# BLOCK1.net
KiCad netlist of a schematic drawn in Altium Designer
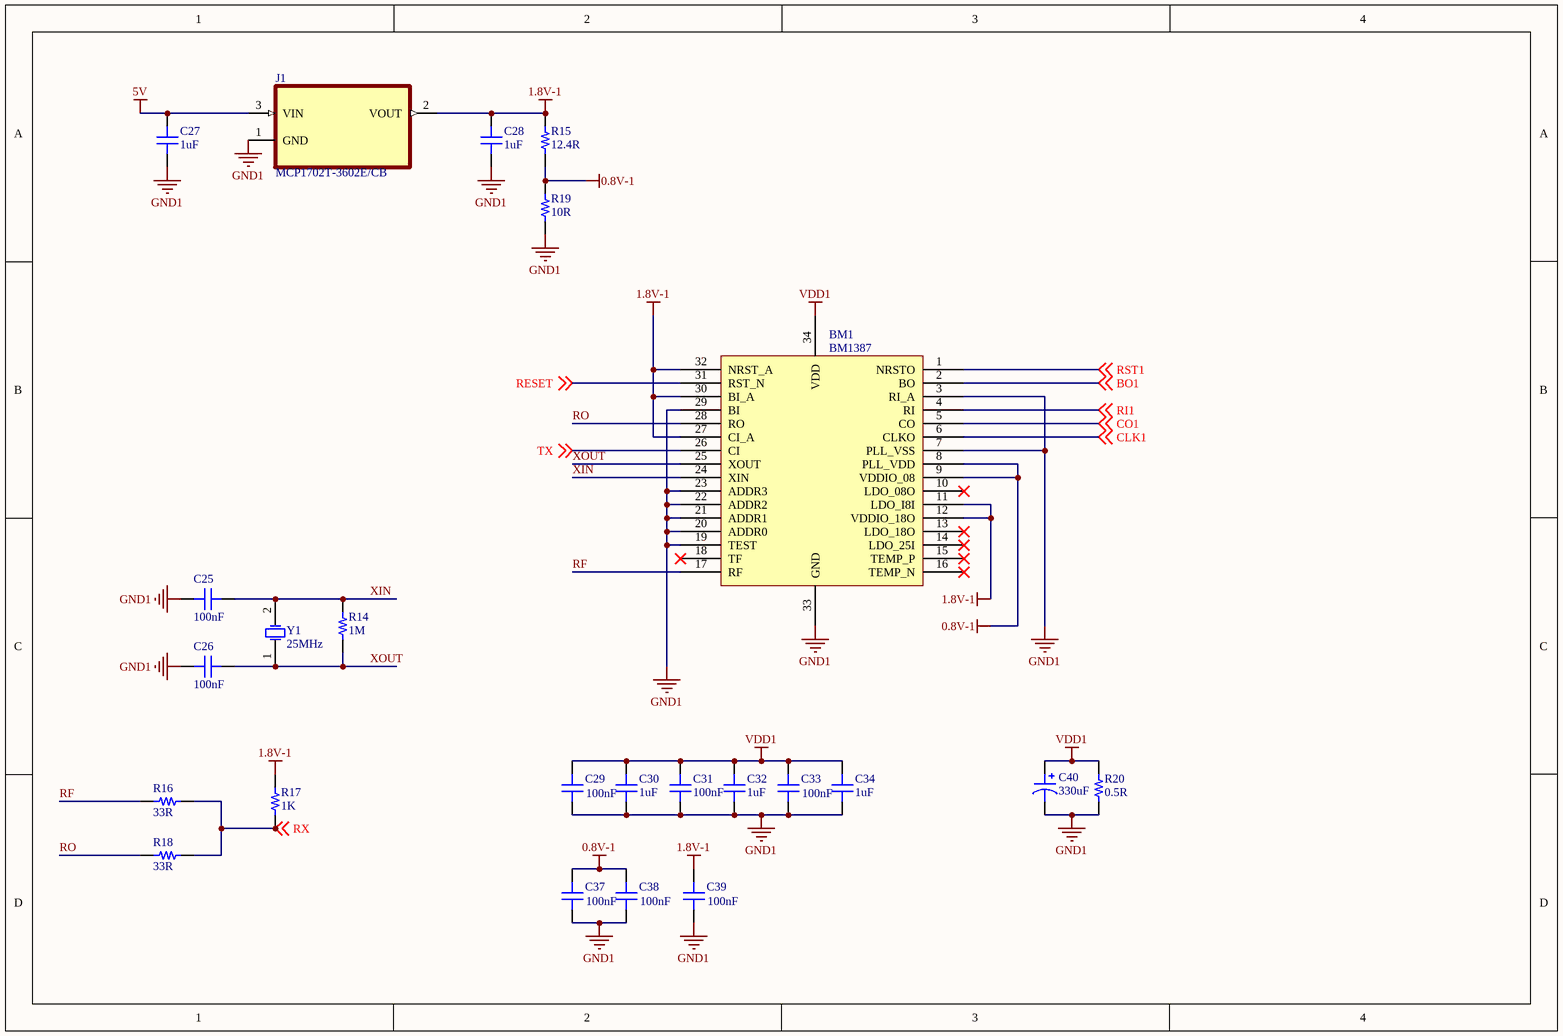
[diagram p0: BLOCK1.SchDoc]

(export (version "E")
  (design (tool "Eeschema 10.0.6"))
  (components
    (comp (ref "BM1") (value "BM1387") (footprint "BM1387") (libsource (lib "USB_MINER") (part "BM1387")))
    (comp (ref "C25") (value "100nF") (footprint "CAP-SMD-0402") (libsource (lib "USB_MINER") (part "CAP")))
    (comp (ref "C26") (value "100nF") (footprint "CAP-SMD-0402") (libsource (lib "USB_MINER") (part "CAP")))
    (comp (ref "C27") (value "1uF") (footprint "CAP-SMD-0402") (libsource (lib "USB_MINER") (part "CAP")))
    (comp (ref "C28") (value "1uF") (footprint "CAP-SMD-0402") (libsource (lib "USB_MINER") (part "CAP")))
    (comp (ref "C29") (value "100nF") (footprint "CAP_SMD_1206") (libsource (lib "USB_MINER") (part "CAP")))
    (comp (ref "C30") (value "1uF") (footprint "CAP_SMD_1206") (libsource (lib "USB_MINER") (part "CAP")))
    (comp (ref "C31") (value "100nF") (footprint "CAP_SMD_1206") (libsource (lib "USB_MINER") (part "CAP")))
    (comp (ref "C32") (value "1uF") (footprint "CAP_SMD_1206") (libsource (lib "USB_MINER") (part "CAP")))
    (comp (ref "C33") (value "100nF") (footprint "CAP_SMD_1206") (libsource (lib "USB_MINER") (part "CAP")))
    (comp (ref "C34") (value "1uF") (footprint "CAP_SMD_1206") (libsource (lib "USB_MINER") (part "CAP")))
    (comp (ref "C37") (value "100nF") (footprint "CAP-SMD-0402") (libsource (lib "USB_MINER") (part "CAP")))
    (comp (ref "C38") (value "100nF") (footprint "CAP-SMD-0402") (libsource (lib "USB_MINER") (part "CAP")))
    (comp (ref "C39") (value "100nF") (footprint "CAP-SMD-0402") (libsource (lib "USB_MINER") (part "CAP")))
    (comp (ref "C40")
      (value "330uF")
      (footprint "CAP-TAN-CASE-E")
      (libsource (lib "USB_MINER") (part "POLARIZED CAP"))
    )
    (comp (ref "J1")
      (value "MCP1702T-3602E/CB")
      (footprint "SOT95P255X145-3N")
      (description "250 mA Low Quiescent Current LDO Regulator")
      (libsource (lib "USB_MINER") (part "MCP1702T-3602E/CB"))
    )
    (comp (ref "R14") (value "1M") (footprint "RES-SMD-0402") (libsource (lib "USB_MINER") (part "RES")))
    (comp (ref "R15") (value "12.4R") (footprint "RES-SMD-0402") (libsource (lib "USB_MINER") (part "RES")))
    (comp (ref "R16") (value "33R") (footprint "RES-SMD-0402") (libsource (lib "USB_MINER") (part "RES")))
    (comp (ref "R17") (value "1K") (footprint "RES-SMD-0402") (libsource (lib "USB_MINER") (part "RES")))
    (comp (ref "R18") (value "33R") (footprint "RES-SMD-0402") (libsource (lib "USB_MINER") (part "RES")))
    (comp (ref "R19") (value "10R") (footprint "RES-SMD-0402") (libsource (lib "USB_MINER") (part "RES")))
    (comp (ref "R20") (value "0.5R") (footprint "RES-SMD-1206") (libsource (lib "USB_MINER") (part "RES")))
    (comp (ref "Y1")
      (value "25MHz")
      (footprint "XTALL")
      (description "Crystal Oscillator")
      (fields (field (name "PUBLISHER") "Altium Limited"))
      (libsource (lib "USB_MINER") (part "XTAL"))
    )
  )
  (nets
    (net (code "1") (name "/RF") (class "Default")
      (node (ref "BM1") (pin "17") (pinfunction "RF_17") (pintype "passive"))
      (node (ref "R16") (pin "1") (pinfunction "1_1") (pintype "passive"))
    )
    (net (code "2") (name "/RO") (class "Default")
      (node (ref "BM1") (pin "28") (pinfunction "RO_28") (pintype "passive"))
      (node (ref "R18") (pin "1") (pinfunction "1_1") (pintype "passive"))
    )
    (net (code "3") (name "/XIN") (class "Default")
      (node (ref "BM1") (pin "24") (pinfunction "XIN_24") (pintype "passive"))
      (node (ref "C25") (pin "2") (pinfunction "2_2") (pintype "passive"))
      (node (ref "R14") (pin "2") (pinfunction "2_2") (pintype "passive"))
      (node (ref "Y1") (pin "2") (pinfunction "OSC2_2") (pintype "passive"))
    )
    (net (code "4") (name "/XOUT") (class "Default")
      (node (ref "BM1") (pin "25") (pinfunction "XOUT_25") (pintype "passive"))
      (node (ref "C26") (pin "2") (pinfunction "2_2") (pintype "passive"))
      (node (ref "R14") (pin "1") (pinfunction "1_1") (pintype "passive"))
      (node (ref "Y1") (pin "1") (pinfunction "OSC1_1") (pintype "passive"))
    )
    (net (code "5") (name "0.8V-1") (class "Default")
      (node (ref "BM1") (pin "8") (pinfunction "PLL_VDD_8") (pintype "passive"))
      (node (ref "BM1") (pin "9") (pinfunction "VDDIO_08_9") (pintype "passive"))
      (node (ref "C37") (pin "2") (pinfunction "2_2") (pintype "passive"))
      (node (ref "C38") (pin "2") (pinfunction "2_2") (pintype "passive"))
      (node (ref "R15") (pin "1") (pinfunction "1_1") (pintype "passive"))
      (node (ref "R19") (pin "2") (pinfunction "2_2") (pintype "passive"))
    )
    (net (code "6") (name "1.8V-1") (class "Default")
      (node (ref "BM1") (pin "11") (pinfunction "LDO_I8I_11") (pintype "passive"))
      (node (ref "BM1") (pin "12") (pinfunction "VDDIO_18O_12") (pintype "passive"))
      (node (ref "BM1") (pin "27") (pinfunction "CI_A_27") (pintype "passive"))
      (node (ref "BM1") (pin "30") (pinfunction "BI_A_30") (pintype "passive"))
      (node (ref "BM1") (pin "32") (pinfunction "NRST_A_32") (pintype "passive"))
      (node (ref "C28") (pin "2") (pinfunction "2_2") (pintype "passive"))
      (node (ref "C39") (pin "2") (pinfunction "2_2") (pintype "passive"))
      (node (ref "J1") (pin "2") (pinfunction "VOUT_2") (pintype "output"))
      (node (ref "R15") (pin "2") (pinfunction "2_2") (pintype "passive"))
      (node (ref "R17") (pin "2") (pinfunction "2_2") (pintype "passive"))
    )
    (net (code "7") (name "5V") (class "Default")
      (node (ref "C27") (pin "2") (pinfunction "2_2") (pintype "passive"))
      (node (ref "J1") (pin "3") (pinfunction "VIN_3") (pintype "input"))
    )
    (net (code "8") (name "BO1") (class "Default")
      (node (ref "BM1") (pin "2") (pinfunction "BO_2") (pintype "passive"))
    )
    (net (code "9") (name "CLK1") (class "Default")
      (node (ref "BM1") (pin "6") (pinfunction "CLKO_6") (pintype "passive"))
    )
    (net (code "10") (name "CO1") (class "Default")
      (node (ref "BM1") (pin "5") (pinfunction "CO_5") (pintype "passive"))
    )
    (net (code "11") (name "GND1") (class "Default")
      (node (ref "BM1") (pin "19") (pinfunction "TEST_19") (pintype "passive"))
      (node (ref "BM1") (pin "20") (pinfunction "ADDR0_20") (pintype "passive"))
      (node (ref "BM1") (pin "21") (pinfunction "ADDR1_21") (pintype "passive"))
      (node (ref "BM1") (pin "22") (pinfunction "ADDR2_22") (pintype "passive"))
      (node (ref "BM1") (pin "23") (pinfunction "ADDR3_23") (pintype "passive"))
      (node (ref "BM1") (pin "29") (pinfunction "BI_29") (pintype "passive"))
      (node (ref "BM1") (pin "3") (pinfunction "RI_A_3") (pintype "passive"))
      (node (ref "BM1") (pin "33") (pinfunction "GND_33") (pintype "passive"))
      (node (ref "BM1") (pin "7") (pinfunction "PLL_VSS_7") (pintype "passive"))
      (node (ref "C25") (pin "1") (pinfunction "1_1") (pintype "passive"))
      (node (ref "C26") (pin "1") (pinfunction "1_1") (pintype "passive"))
      (node (ref "C27") (pin "1") (pinfunction "1_1") (pintype "passive"))
      (node (ref "C28") (pin "1") (pinfunction "1_1") (pintype "passive"))
      (node (ref "C29") (pin "1") (pinfunction "1_1") (pintype "passive"))
      (node (ref "C30") (pin "1") (pinfunction "1_1") (pintype "passive"))
      (node (ref "C31") (pin "1") (pinfunction "1_1") (pintype "passive"))
      (node (ref "C32") (pin "1") (pinfunction "1_1") (pintype "passive"))
      (node (ref "C33") (pin "1") (pinfunction "1_1") (pintype "passive"))
      (node (ref "C34") (pin "1") (pinfunction "1_1") (pintype "passive"))
      (node (ref "C37") (pin "1") (pinfunction "1_1") (pintype "passive"))
      (node (ref "C38") (pin "1") (pinfunction "1_1") (pintype "passive"))
      (node (ref "C39") (pin "1") (pinfunction "1_1") (pintype "passive"))
      (node (ref "C40") (pin "2") (pinfunction "2_2") (pintype "passive"))
      (node (ref "J1") (pin "1") (pinfunction "GND_1") (pintype "passive"))
      (node (ref "R19") (pin "1") (pinfunction "1_1") (pintype "passive"))
      (node (ref "R20") (pin "1") (pinfunction "1_1") (pintype "passive"))
    )
    (net (code "12") (name "RESET") (class "Default")
      (node (ref "BM1") (pin "31") (pinfunction "RST_N_31") (pintype "passive"))
    )
    (net (code "13") (name "RI1") (class "Default")
      (node (ref "BM1") (pin "4") (pinfunction "RI_4") (pintype "passive"))
    )
    (net (code "14") (name "RST1") (class "Default")
      (node (ref "BM1") (pin "1") (pinfunction "NRSTO_1") (pintype "passive"))
    )
    (net (code "15") (name "RX") (class "Default")
      (node (ref "R16") (pin "2") (pinfunction "2_2") (pintype "passive"))
      (node (ref "R17") (pin "1") (pinfunction "1_1") (pintype "passive"))
      (node (ref "R18") (pin "2") (pinfunction "2_2") (pintype "passive"))
    )
    (net (code "16") (name "TX") (class "Default")
      (node (ref "BM1") (pin "26") (pinfunction "CI_26") (pintype "passive"))
    )
    (net (code "17") (name "VDD1") (class "Default")
      (node (ref "BM1") (pin "34") (pinfunction "VDD_34") (pintype "passive"))
      (node (ref "C29") (pin "2") (pinfunction "2_2") (pintype "passive"))
      (node (ref "C30") (pin "2") (pinfunction "2_2") (pintype "passive"))
      (node (ref "C31") (pin "2") (pinfunction "2_2") (pintype "passive"))
      (node (ref "C32") (pin "2") (pinfunction "2_2") (pintype "passive"))
      (node (ref "C33") (pin "2") (pinfunction "2_2") (pintype "passive"))
      (node (ref "C34") (pin "2") (pinfunction "2_2") (pintype "passive"))
      (node (ref "C40") (pin "1") (pinfunction "1_1") (pintype "passive"))
      (node (ref "R20") (pin "2") (pinfunction "2_2") (pintype "passive"))
    )
    (net (code "18") (name "unconnected-(BM1-LDO_08O-Pad10)") (class "Default")
      (node (ref "BM1") (pin "10") (pinfunction "LDO_08O_10") (pintype "passive+no_connect"))
    )
    (net (code "19") (name "unconnected-(BM1-LDO_18O-Pad13)") (class "Default")
      (node (ref "BM1") (pin "13") (pinfunction "LDO_18O_13") (pintype "passive+no_connect"))
    )
    (net (code "20") (name "unconnected-(BM1-LDO_25I-Pad14)") (class "Default")
      (node (ref "BM1") (pin "14") (pinfunction "LDO_25I_14") (pintype "passive+no_connect"))
    )
    (net (code "21") (name "unconnected-(BM1-TEMP_N-Pad16)") (class "Default")
      (node (ref "BM1") (pin "16") (pinfunction "TEMP_N_16") (pintype "passive+no_connect"))
    )
    (net (code "22") (name "unconnected-(BM1-TEMP_P-Pad15)") (class "Default")
      (node (ref "BM1") (pin "15") (pinfunction "TEMP_P_15") (pintype "passive+no_connect"))
    )
    (net (code "23") (name "unconnected-(BM1-TF-Pad18)") (class "Default")
      (node (ref "BM1") (pin "18") (pinfunction "TF_18") (pintype "passive+no_connect"))
    )
  )
)
